# avr328.net
KiCad netlist of a schematic drawn in EAGLE
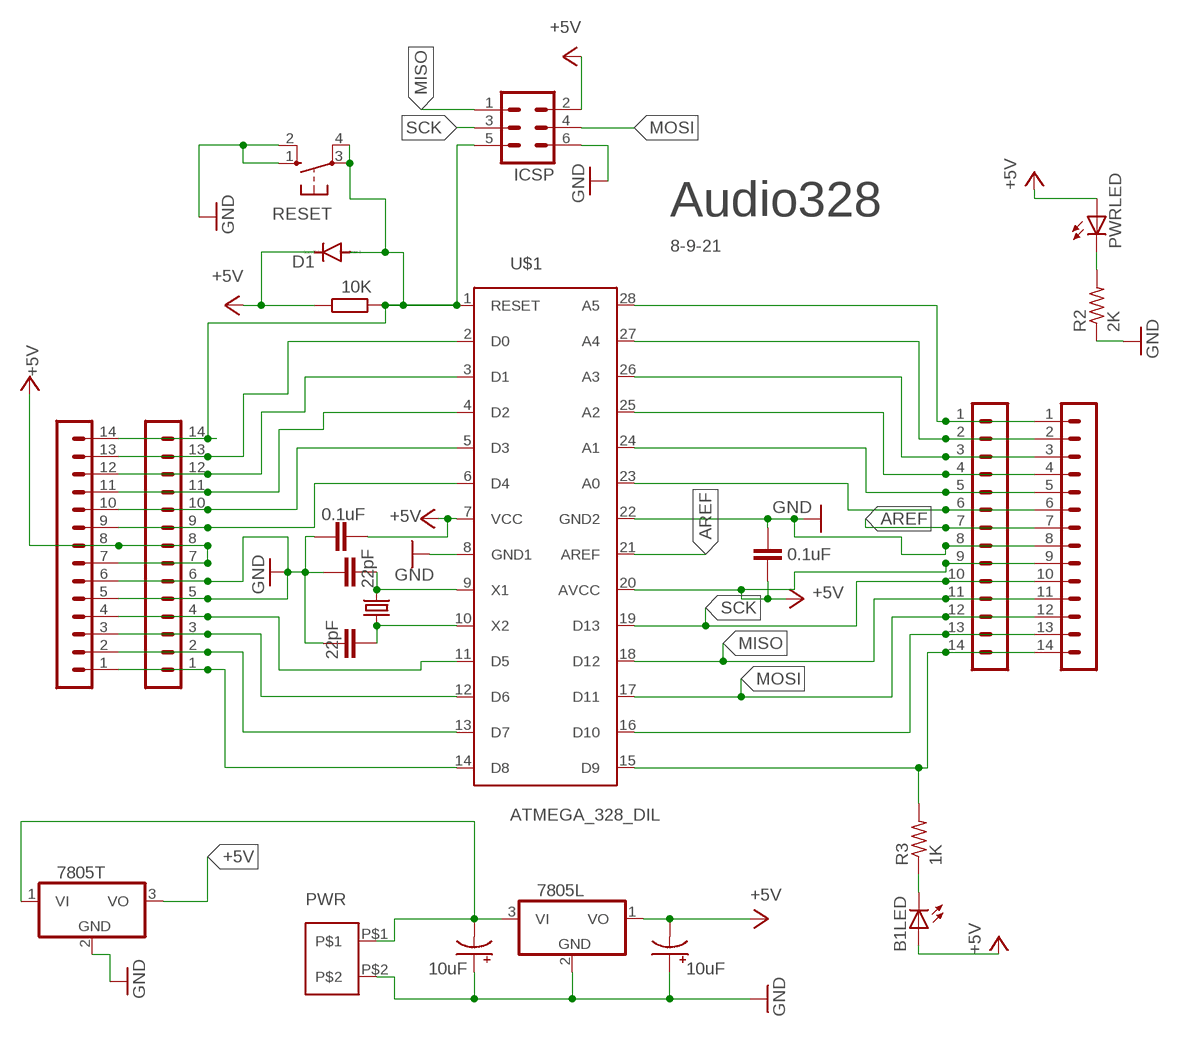
[diagram p0: schematic, sheet 1]

(export (version "E")
  (design (tool "Eeschema 10.0.6"))
  (components
    (comp (ref "-")
      (value "14_PIN_CONN")
      (footprint "eagle-import:14_PIN_CONN")
      (libsource (lib "eagle-import") (part "14_PIN_CONN"))
    )
    (comp (ref ".")
      (value "14_PIN_CONN")
      (footprint "eagle-import:14_PIN_CONN")
      (libsource (lib "eagle-import") (part "14_PIN_CONN"))
    )
    (comp (ref ".-")
      (value "14_PIN_CONN")
      (footprint "eagle-import:14_PIN_CONN")
      (libsource (lib "eagle-import") (part "14_PIN_CONN"))
    )
    (comp (ref "..")
      (value "14_PIN_CONN")
      (footprint "eagle-import:14_PIN_CONN")
      (libsource (lib "eagle-import") (part "14_PIN_CONN"))
    )
    (comp (ref "B1LED")
      (value "LED3MM")
      (footprint "eagle-import:LED3MM")
      (libsource (lib "eagle-import") (part "LED3MM"))
    )
    (comp (ref "C1")
      (value "22pF")
      (footprint "eagle-import:C025-024X044")
      (libsource (lib "eagle-import") (part "C-EU025-024X044"))
    )
    (comp (ref "C2")
      (value "22pF")
      (footprint "eagle-import:C025-024X044")
      (libsource (lib "eagle-import") (part "C-EU025-024X044"))
    )
    (comp (ref "C3")
      (value "0.1uF")
      (footprint "eagle-import:C025-024X044")
      (libsource (lib "eagle-import") (part "C-EU025-024X044"))
    )
    (comp (ref "C5")
      (value "0.1uF")
      (footprint "eagle-import:C025-024X044")
      (libsource (lib "eagle-import") (part "C-EU025-024X044"))
    )
    (comp (ref "C7")
      (value "10uF")
      (footprint "eagle-import:E2-5")
      (libsource (lib "eagle-import") (part "CPOL-USE2-5"))
    )
    (comp (ref "C8")
      (value "10uF")
      (footprint "eagle-import:E2-5")
      (libsource (lib "eagle-import") (part "CPOL-USE2-5"))
    )
    (comp (ref "D1")
      (value "1N4148DO35-7")
      (footprint "eagle-import:DO35-7")
      (libsource (lib "eagle-import") (part "1N4148DO35-7"))
    )
    (comp (ref "IC1")
      (value "7805L")
      (footprint "eagle-import:TO92")
      (libsource (lib "eagle-import") (part "78L05"))
    )
    (comp (ref "IC2")
      (value "7805T")
      (footprint "eagle-import:TO220H")
      (libsource (lib "eagle-import") (part "78T05"))
    )
    (comp (ref "ICSP")
      (value "MA03-2")
      (footprint "eagle-import:MA03-2")
      (libsource (lib "eagle-import") (part "MA03-2"))
    )
    (comp (ref "PWR")
      (value "PWR")
      (footprint "eagle-import:2_PIN_SCREW_CONN")
      (libsource (lib "eagle-import") (part "2_PIN_SCREW_CONN"))
    )
    (comp (ref "PWRLED")
      (value "LED3MM")
      (footprint "eagle-import:LED3MM")
      (libsource (lib "eagle-import") (part "LED3MM"))
    )
    (comp (ref "R1")
      (value "10K")
      (footprint "eagle-import:0207_10")
      (libsource (lib "eagle-import") (part "R-EU_0207/10"))
    )
    (comp (ref "R2")
      (value "2K")
      (footprint "eagle-import:0204_5")
      (libsource (lib "eagle-import") (part "R-US_0204/5"))
    )
    (comp (ref "R3")
      (value "1K")
      (footprint "eagle-import:0204_5")
      (libsource (lib "eagle-import") (part "R-US_0204/5"))
    )
    (comp (ref "RESET")
      (value "10-XX")
      (footprint "eagle-import:B3F-10XX")
      (fields (field (name "MPN") "B3F-1000"))
      (libsource (lib "eagle-import") (part "10-XX"))
    )
    (comp (ref "U$1")
      (value "ATMEGA_328_DIL")
      (footprint "eagle-import:ATMEGA_328_DIL")
      (libsource (lib "eagle-import") (part "ATMEGA_328_DIL"))
    )
    (comp (ref "Y1")
      (value "CRYSTALHC49UV")
      (footprint "eagle-import:HC49U-V")
      (libsource (lib "eagle-import") (part "CRYSTALHC49UV"))
    )
  )
  (nets
    (net (code "1") (name "+5V") (class "Default")
      (node (ref "-") (pin "9") (pinfunction "9_9") (pintype "passive"))
      (node (ref ".") (pin "7") (pinfunction "7_7") (pintype "passive"))
      (node (ref ".") (pin "8") (pinfunction "8_8") (pintype "passive"))
      (node (ref ".-") (pin "9") (pinfunction "9_9") (pintype "passive"))
      (node (ref "..") (pin "7") (pinfunction "7_7") (pintype "passive"))
      (node (ref "..") (pin "8") (pinfunction "8_8") (pintype "passive"))
      (node (ref "B1LED") (pin "A") (pinfunction "A_A") (pintype "passive"))
      (node (ref "C3") (pin "2") (pinfunction "2_2") (pintype "passive"))
      (node (ref "C5") (pin "2") (pinfunction "2_2") (pintype "passive"))
      (node (ref "C7") (pin "-") (pinfunction "-_-") (pintype "passive"))
      (node (ref "D1") (pin "C") (pinfunction "C_C") (pintype "passive"))
      (node (ref "IC1") (pin "1") (pinfunction "VO_1") (pintype "passive"))
      (node (ref "IC2") (pin "3") (pinfunction "VO_3") (pintype "passive"))
      (node (ref "ICSP") (pin "2") (pinfunction "2_2") (pintype "passive"))
      (node (ref "PWRLED") (pin "A") (pinfunction "A_A") (pintype "passive"))
      (node (ref "R1") (pin "1") (pinfunction "1_1") (pintype "passive"))
      (node (ref "U$1") (pin "20") (pinfunction "AVCC_20") (pintype "bidirectional"))
      (node (ref "U$1") (pin "7") (pinfunction "VCC_7") (pintype "bidirectional"))
    )
    (net (code "2") (name "AREF") (class "Default")
      (node (ref "-") (pin "7") (pinfunction "7_7") (pintype "passive"))
      (node (ref ".-") (pin "7") (pinfunction "7_7") (pintype "passive"))
      (node (ref "U$1") (pin "21") (pinfunction "AREF_21") (pintype "bidirectional"))
    )
    (net (code "3") (name "GND") (class "Default")
      (node (ref "-") (pin "8") (pinfunction "8_8") (pintype "passive"))
      (node (ref ".") (pin "5") (pinfunction "5_5") (pintype "passive"))
      (node (ref ".") (pin "6") (pinfunction "6_6") (pintype "passive"))
      (node (ref ".-") (pin "8") (pinfunction "8_8") (pintype "passive"))
      (node (ref "..") (pin "5") (pinfunction "5_5") (pintype "passive"))
      (node (ref "..") (pin "6") (pinfunction "6_6") (pintype "passive"))
      (node (ref "C1") (pin "1") (pinfunction "1_1") (pintype "passive"))
      (node (ref "C2") (pin "1") (pinfunction "1_1") (pintype "passive"))
      (node (ref "C3") (pin "1") (pinfunction "1_1") (pintype "passive"))
      (node (ref "C5") (pin "1") (pinfunction "1_1") (pintype "passive"))
      (node (ref "C7") (pin "+") (pinfunction "+_+") (pintype "passive"))
      (node (ref "C8") (pin "+") (pinfunction "+_+") (pintype "passive"))
      (node (ref "IC1") (pin "2") (pinfunction "GND_2") (pintype "passive"))
      (node (ref "IC2") (pin "2") (pinfunction "GND_2") (pintype "passive"))
      (node (ref "ICSP") (pin "6") (pinfunction "6_6") (pintype "passive"))
      (node (ref "PWR") (pin "P$2") (pinfunction "P$2_P$2") (pintype "bidirectional"))
      (node (ref "R2") (pin "1") (pinfunction "1_1") (pintype "passive"))
      (node (ref "RESET") (pin "1") (pinfunction "S_1") (pintype "passive"))
      (node (ref "RESET") (pin "2") (pinfunction "S1_2") (pintype "passive"))
      (node (ref "U$1") (pin "22") (pinfunction "GND2_22") (pintype "bidirectional"))
      (node (ref "U$1") (pin "8") (pinfunction "GND1_8") (pintype "bidirectional"))
    )
    (net (code "4") (name "MISO") (class "Default")
      (node (ref "-") (pin "11") (pinfunction "11_11") (pintype "passive"))
      (node (ref ".-") (pin "11") (pinfunction "11_11") (pintype "passive"))
      (node (ref "ICSP") (pin "1") (pinfunction "1_1") (pintype "passive"))
      (node (ref "U$1") (pin "18") (pinfunction "D12_18") (pintype "bidirectional"))
    )
    (net (code "5") (name "MOSI") (class "Default")
      (node (ref "-") (pin "12") (pinfunction "12_12") (pintype "passive"))
      (node (ref ".-") (pin "12") (pinfunction "12_12") (pintype "passive"))
      (node (ref "ICSP") (pin "4") (pinfunction "4_4") (pintype "passive"))
      (node (ref "U$1") (pin "17") (pinfunction "D11_17") (pintype "bidirectional"))
    )
    (net (code "6") (name "Net-(B1LED-C)") (class "Default")
      (node (ref "B1LED") (pin "K") (pinfunction "C_K") (pintype "passive"))
      (node (ref "R3") (pin "1") (pinfunction "1_1") (pintype "passive"))
    )
    (net (code "7") (name "Net-(IC1-VI)") (class "Default")
      (node (ref "C8") (pin "-") (pinfunction "-_-") (pintype "passive"))
      (node (ref "IC1") (pin "3") (pinfunction "VI_3") (pintype "input"))
      (node (ref "IC2") (pin "1") (pinfunction "VI_1") (pintype "input"))
      (node (ref "PWR") (pin "P$1") (pinfunction "P$1_P$1") (pintype "bidirectional"))
    )
    (net (code "8") (name "Net-(PWRLED-C)") (class "Default")
      (node (ref "PWRLED") (pin "K") (pinfunction "C_K") (pintype "passive"))
      (node (ref "R2") (pin "2") (pinfunction "2_2") (pintype "passive"))
    )
    (net (code "9") (name "Net-(RESET-P)") (class "Default")
      (node (ref ".") (pin "14") (pinfunction "14_14") (pintype "passive"))
      (node (ref "..") (pin "14") (pinfunction "14_14") (pintype "passive"))
      (node (ref "D1") (pin "A") (pinfunction "A_A") (pintype "passive"))
      (node (ref "ICSP") (pin "5") (pinfunction "5_5") (pintype "passive"))
      (node (ref "R1") (pin "2") (pinfunction "2_2") (pintype "passive"))
      (node (ref "RESET") (pin "3") (pinfunction "P_3") (pintype "passive"))
      (node (ref "RESET") (pin "4") (pinfunction "P1_4") (pintype "passive"))
      (node (ref "U$1") (pin "1") (pinfunction "RESET_1") (pintype "bidirectional"))
    )
    (net (code "10") (name "Net-(U$1-A0)") (class "Default")
      (node (ref "-") (pin "6") (pinfunction "6_6") (pintype "passive"))
      (node (ref ".-") (pin "6") (pinfunction "6_6") (pintype "passive"))
      (node (ref "U$1") (pin "23") (pinfunction "A0_23") (pintype "bidirectional"))
    )
    (net (code "11") (name "Net-(U$1-A1)") (class "Default")
      (node (ref "-") (pin "5") (pinfunction "5_5") (pintype "passive"))
      (node (ref ".-") (pin "5") (pinfunction "5_5") (pintype "passive"))
      (node (ref "U$1") (pin "24") (pinfunction "A1_24") (pintype "bidirectional"))
    )
    (net (code "12") (name "Net-(U$1-A2)") (class "Default")
      (node (ref "-") (pin "4") (pinfunction "4_4") (pintype "passive"))
      (node (ref ".-") (pin "4") (pinfunction "4_4") (pintype "passive"))
      (node (ref "U$1") (pin "25") (pinfunction "A2_25") (pintype "bidirectional"))
    )
    (net (code "13") (name "Net-(U$1-A3)") (class "Default")
      (node (ref "-") (pin "3") (pinfunction "3_3") (pintype "passive"))
      (node (ref ".-") (pin "3") (pinfunction "3_3") (pintype "passive"))
      (node (ref "U$1") (pin "26") (pinfunction "A3_26") (pintype "bidirectional"))
    )
    (net (code "14") (name "Net-(U$1-A4)") (class "Default")
      (node (ref "-") (pin "2") (pinfunction "2_2") (pintype "passive"))
      (node (ref ".-") (pin "2") (pinfunction "2_2") (pintype "passive"))
      (node (ref "U$1") (pin "27") (pinfunction "A4_27") (pintype "bidirectional"))
    )
    (net (code "15") (name "Net-(U$1-A5)") (class "Default")
      (node (ref "-") (pin "1") (pinfunction "1_1") (pintype "passive"))
      (node (ref ".-") (pin "1") (pinfunction "1_1") (pintype "passive"))
      (node (ref "U$1") (pin "28") (pinfunction "A5_28") (pintype "bidirectional"))
    )
    (net (code "16") (name "Net-(U$1-D0)") (class "Default")
      (node (ref ".") (pin "13") (pinfunction "13_13") (pintype "passive"))
      (node (ref "..") (pin "13") (pinfunction "13_13") (pintype "passive"))
      (node (ref "U$1") (pin "2") (pinfunction "D0_2") (pintype "bidirectional"))
    )
    (net (code "17") (name "Net-(U$1-D1)") (class "Default")
      (node (ref ".") (pin "12") (pinfunction "12_12") (pintype "passive"))
      (node (ref "..") (pin "12") (pinfunction "12_12") (pintype "passive"))
      (node (ref "U$1") (pin "3") (pinfunction "D1_3") (pintype "bidirectional"))
    )
    (net (code "18") (name "Net-(U$1-D2)") (class "Default")
      (node (ref ".") (pin "11") (pinfunction "11_11") (pintype "passive"))
      (node (ref "..") (pin "11") (pinfunction "11_11") (pintype "passive"))
      (node (ref "U$1") (pin "4") (pinfunction "D2_4") (pintype "bidirectional"))
    )
    (net (code "19") (name "Net-(U$1-D3)") (class "Default")
      (node (ref ".") (pin "10") (pinfunction "10_10") (pintype "passive"))
      (node (ref "..") (pin "10") (pinfunction "10_10") (pintype "passive"))
      (node (ref "U$1") (pin "5") (pinfunction "D3_5") (pintype "bidirectional"))
    )
    (net (code "20") (name "Net-(U$1-D4)") (class "Default")
      (node (ref ".") (pin "9") (pinfunction "9_9") (pintype "passive"))
      (node (ref "..") (pin "9") (pinfunction "9_9") (pintype "passive"))
      (node (ref "U$1") (pin "6") (pinfunction "D4_6") (pintype "bidirectional"))
    )
    (net (code "21") (name "Net-(U$1-D5)") (class "Default")
      (node (ref ".") (pin "4") (pinfunction "4_4") (pintype "passive"))
      (node (ref "..") (pin "4") (pinfunction "4_4") (pintype "passive"))
      (node (ref "U$1") (pin "11") (pinfunction "D5_11") (pintype "bidirectional"))
    )
    (net (code "22") (name "Net-(U$1-D6)") (class "Default")
      (node (ref ".") (pin "3") (pinfunction "3_3") (pintype "passive"))
      (node (ref "..") (pin "3") (pinfunction "3_3") (pintype "passive"))
      (node (ref "U$1") (pin "12") (pinfunction "D6_12") (pintype "bidirectional"))
    )
    (net (code "23") (name "Net-(U$1-D7)") (class "Default")
      (node (ref ".") (pin "2") (pinfunction "2_2") (pintype "passive"))
      (node (ref "..") (pin "2") (pinfunction "2_2") (pintype "passive"))
      (node (ref "U$1") (pin "13") (pinfunction "D7_13") (pintype "bidirectional"))
    )
    (net (code "24") (name "Net-(U$1-D8)") (class "Default")
      (node (ref ".") (pin "1") (pinfunction "1_1") (pintype "passive"))
      (node (ref "..") (pin "1") (pinfunction "1_1") (pintype "passive"))
      (node (ref "U$1") (pin "14") (pinfunction "D8_14") (pintype "bidirectional"))
    )
    (net (code "25") (name "Net-(U$1-D9)") (class "Default")
      (node (ref "-") (pin "14") (pinfunction "14_14") (pintype "passive"))
      (node (ref ".-") (pin "14") (pinfunction "14_14") (pintype "passive"))
      (node (ref "R3") (pin "2") (pinfunction "2_2") (pintype "passive"))
      (node (ref "U$1") (pin "15") (pinfunction "D9_15") (pintype "bidirectional"))
    )
    (net (code "26") (name "Net-(U$1-D10)") (class "Default")
      (node (ref "-") (pin "13") (pinfunction "13_13") (pintype "passive"))
      (node (ref ".-") (pin "13") (pinfunction "13_13") (pintype "passive"))
      (node (ref "U$1") (pin "16") (pinfunction "D10_16") (pintype "bidirectional"))
    )
    (net (code "27") (name "Net-(U$1-X1)") (class "Default")
      (node (ref "C1") (pin "2") (pinfunction "2_2") (pintype "passive"))
      (node (ref "U$1") (pin "9") (pinfunction "X1_9") (pintype "bidirectional"))
      (node (ref "Y1") (pin "2") (pinfunction "2_2") (pintype "passive"))
    )
    (net (code "28") (name "Net-(U$1-X2)") (class "Default")
      (node (ref "C2") (pin "2") (pinfunction "2_2") (pintype "passive"))
      (node (ref "U$1") (pin "10") (pinfunction "X2_10") (pintype "bidirectional"))
      (node (ref "Y1") (pin "1") (pinfunction "1_1") (pintype "passive"))
    )
    (net (code "29") (name "SCK") (class "Default")
      (node (ref "-") (pin "10") (pinfunction "10_10") (pintype "passive"))
      (node (ref ".-") (pin "10") (pinfunction "10_10") (pintype "passive"))
      (node (ref "ICSP") (pin "3") (pinfunction "3_3") (pintype "passive"))
      (node (ref "U$1") (pin "19") (pinfunction "D13_19") (pintype "bidirectional"))
    )
  )
)
